# 24VBuckBoostConverterSM.net
KiCad netlist of a schematic drawn in Altium Designer
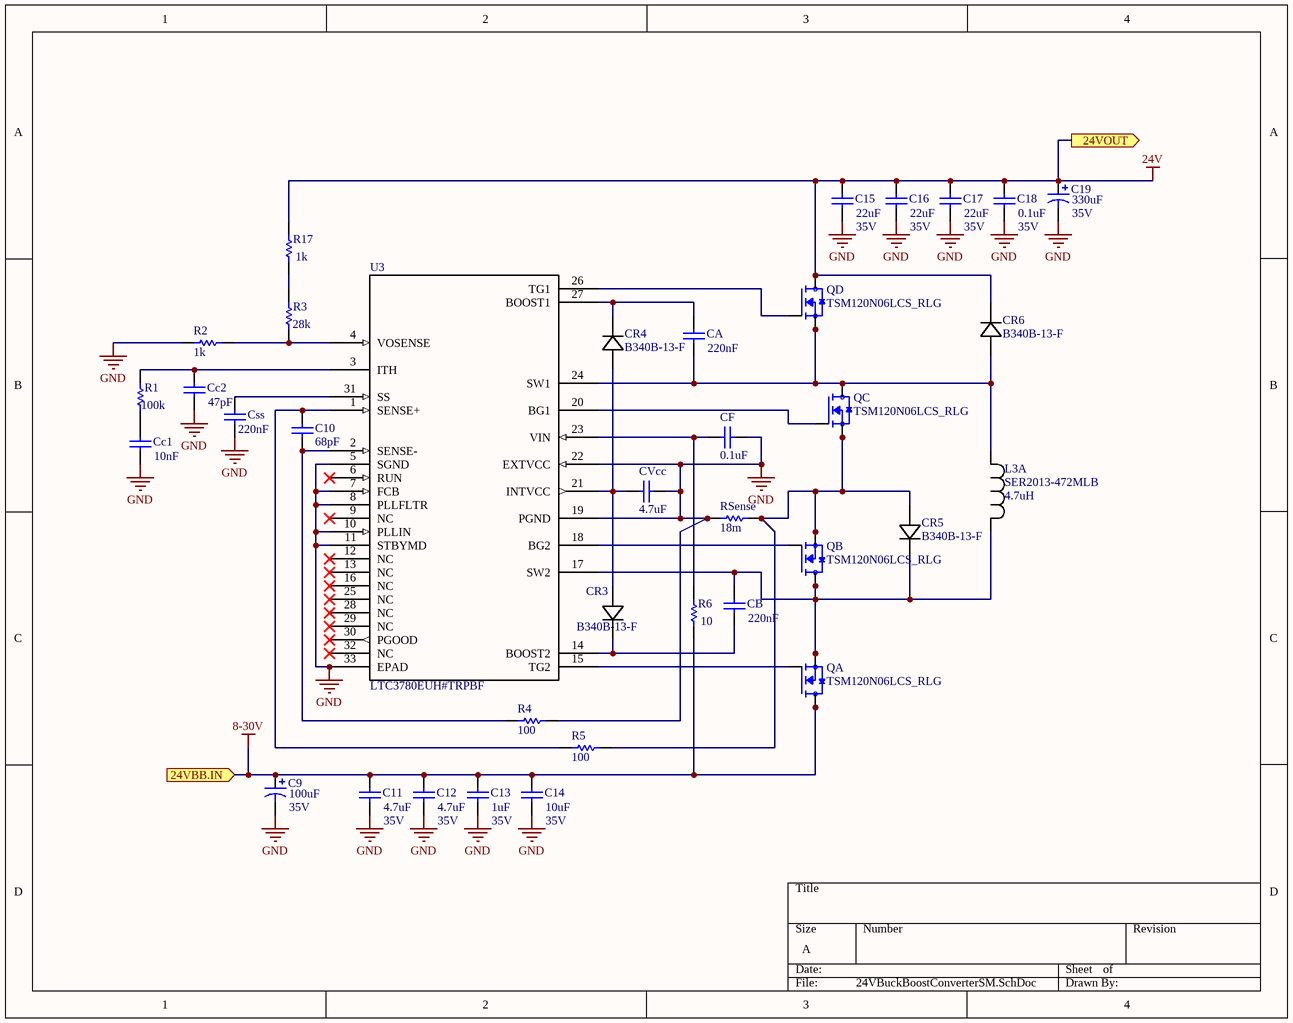
[diagram p0: 24VBuckBoostConverterSM.SchDoc]

(export (version "E")
  (design (tool "Eeschema 10.0.6"))
  (components
    (comp (ref "C9")
      (value "100uF")
      (footprint "RB7.6-15")
      (description "Polarized Capacitor (Radial)")
      (fields
        (field (name "VOLTAGE RATING") "35V")
        (field (name "Comment") "Cap Pol1")
        (field (name "PUBLISHER") "Altium Limited")
      )
      (libsource (lib "Miscellaneous Devices") (part "Cap Pol1"))
    )
    (comp (ref "C10")
      (value "68pF")
      (footprint "RAD-0.1")
      (description "Capacitor")
      (fields (field (name "Comment") "Cap") (field (name "PUBLISHER") "Altium Limited"))
      (libsource (lib "Miscellaneous Devices") (part "Cap"))
    )
    (comp (ref "C11")
      (value "4.7uF")
      (footprint "RAD-0.3")
      (description "Capacitor")
      (fields
        (field (name "VOLTAGE RATING") "35V")
        (field (name "Comment") "Cap")
        (field (name "PUBLISHER") "Altium Limited")
      )
      (libsource (lib "Miscellaneous Devices") (part "Cap"))
    )
    (comp (ref "C12")
      (value "4.7uF")
      (footprint "RAD-0.3")
      (description "Capacitor")
      (fields
        (field (name "VOLTAGE RATING") "35V")
        (field (name "Comment") "Cap")
        (field (name "PUBLISHER") "Altium Limited")
      )
      (libsource (lib "Miscellaneous Devices") (part "Cap"))
    )
    (comp (ref "C13")
      (value "1uF")
      (footprint "RAD-0.3")
      (description "Capacitor")
      (fields
        (field (name "VOLTAGE RATING") "35V")
        (field (name "Comment") "Cap")
        (field (name "PUBLISHER") "Altium Limited")
      )
      (libsource (lib "Miscellaneous Devices") (part "Cap"))
    )
    (comp (ref "C14")
      (value "10uF")
      (footprint "RAD-0.3")
      (description "Capacitor")
      (fields
        (field (name "VOLTAGE RATING") "35V")
        (field (name "Comment") "Cap")
        (field (name "PUBLISHER") "Altium Limited")
      )
      (libsource (lib "Miscellaneous Devices") (part "Cap"))
    )
    (comp (ref "C15")
      (value "22uF")
      (footprint "RAD-0.3")
      (description "Capacitor")
      (fields
        (field (name "VOLTAGE RATING") "35V")
        (field (name "Comment") "Cap")
        (field (name "PUBLISHER") "Altium Limited")
      )
      (libsource (lib "Miscellaneous Devices") (part "Cap"))
    )
    (comp (ref "C16")
      (value "22uF")
      (footprint "RAD-0.3")
      (description "Capacitor")
      (fields
        (field (name "VOLTAGE RATING") "35V")
        (field (name "Comment") "Cap")
        (field (name "PUBLISHER") "Altium Limited")
      )
      (libsource (lib "Miscellaneous Devices") (part "Cap"))
    )
    (comp (ref "C17")
      (value "22uF")
      (footprint "RAD-0.3")
      (description "Capacitor")
      (fields
        (field (name "VOLTAGE RATING") "35V")
        (field (name "Comment") "Cap")
        (field (name "PUBLISHER") "Altium Limited")
      )
      (libsource (lib "Miscellaneous Devices") (part "Cap"))
    )
    (comp (ref "C18")
      (value "0.1uF")
      (footprint "RAD-0.3")
      (description "Capacitor")
      (fields
        (field (name "VOLTAGE RATING") "35V")
        (field (name "Comment") "Cap")
        (field (name "PUBLISHER") "Altium Limited")
      )
      (libsource (lib "Miscellaneous Devices") (part "Cap"))
    )
    (comp (ref "C19")
      (value "330uF")
      (footprint "RB7.6-15")
      (description "Polarized Capacitor (Radial)")
      (fields
        (field (name "VOLTAGE RATING") "35V")
        (field (name "Comment") "Cap Pol1")
        (field (name "PUBLISHER") "Altium Limited")
      )
      (libsource (lib "Miscellaneous Devices") (part "Cap Pol1"))
    )
    (comp (ref "CA")
      (value "220nF")
      (footprint "RAD-0.1")
      (description "Capacitor")
      (fields (field (name "Comment") "Cap") (field (name "PUBLISHER") "Altium Limited"))
      (libsource (lib "Miscellaneous Devices") (part "Cap"))
    )
    (comp (ref "CB")
      (value "220nF")
      (footprint "RAD-0.1")
      (description "Capacitor")
      (fields (field (name "Comment") "Cap") (field (name "PUBLISHER") "Altium Limited"))
      (libsource (lib "Miscellaneous Devices") (part "Cap"))
    )
    (comp (ref "Cc1")
      (value "10nF")
      (footprint "RAD-0.1")
      (description "Capacitor")
      (fields (field (name "Comment") "Cap") (field (name "PUBLISHER") "Altium Limited"))
      (libsource (lib "Miscellaneous Devices") (part "Cap"))
    )
    (comp (ref "Cc2")
      (value "47pF")
      (footprint "RAD-0.2")
      (description "Capacitor")
      (fields (field (name "Comment") "Cap") (field (name "PUBLISHER") "Altium Limited"))
      (libsource (lib "Miscellaneous Devices") (part "Cap"))
    )
    (comp (ref "CF")
      (value "0.1uF")
      (footprint "RAD-0.1")
      (description "Capacitor")
      (fields (field (name "Comment") "Cap") (field (name "PUBLISHER") "Altium Limited"))
      (libsource (lib "Miscellaneous Devices") (part "Cap"))
    )
    (comp (ref "CR3")
      (value "B340B-13-F")
      (footprint "B340A-13-F")
      (description "No Description Available")
      (fields (field (name "COPYRIGHT") "Copyright (C) 2022 Ultra Librarian. All rights reserved."))
      (libsource (lib "B340B-13-F") (part "B340B-13-F"))
    )
    (comp (ref "CR4")
      (value "B340B-13-F")
      (footprint "B340A-13-F")
      (description "No Description Available")
      (fields (field (name "COPYRIGHT") "Copyright (C) 2022 Ultra Librarian. All rights reserved."))
      (libsource (lib "B340B-13-F") (part "B340B-13-F"))
    )
    (comp (ref "CR5")
      (value "B340B-13-F")
      (footprint "B340A-13-F")
      (description "No Description Available")
      (fields (field (name "COPYRIGHT") "Copyright (C) 2022 Ultra Librarian. All rights reserved."))
      (libsource (lib "B340B-13-F") (part "B340B-13-F"))
    )
    (comp (ref "CR6")
      (value "B340B-13-F")
      (footprint "B340A-13-F")
      (description "No Description Available")
      (fields (field (name "COPYRIGHT") "Copyright (C) 2022 Ultra Librarian. All rights reserved."))
      (libsource (lib "B340B-13-F") (part "B340B-13-F"))
    )
    (comp (ref "Css")
      (value "220nF")
      (footprint "RAD-0.1")
      (description "Capacitor")
      (fields (field (name "Comment") "Cap") (field (name "PUBLISHER") "Altium Limited"))
      (libsource (lib "Miscellaneous Devices") (part "Cap"))
    )
    (comp (ref "CVcc")
      (value "4.7uF")
      (footprint "RAD-0.1")
      (description "Capacitor")
      (fields (field (name "Comment") "Cap") (field (name "PUBLISHER") "Altium Limited"))
      (libsource (lib "Miscellaneous Devices") (part "Cap"))
    )
    (comp (ref "L3")
      (value "SER2013-472MLB")
      (footprint "SER2013-472MLB")
      (description "No Description Available")
      (fields
        (field (name "ALTIUM_VALUE") "4.7uH")
        (field (name "COPYRIGHT") "Copyright (C) 2022 Ultra Librarian. All rights reserved.")
      )
      (libsource (lib "SER2013-472MLB") (part "SER2013-472MLB"))
    )
    (comp (ref "QA")
      (value "TSM120N06LCS_RLG")
      (footprint "SOP127P600X200-8N")
      (description "60V, 23A, Single N-Channel Power MOSFET")
      (fields
        (field (name "MF") "Taiwan Semiconductor")
        (field (name "DIGI-KEY_PART_NUMBER") "TSM120N06LCSRLGTR-ND")
      )
      (libsource (lib "TSM120N06LCS_RLG") (part "TSM120N06LCS_RLG"))
    )
    (comp (ref "QB")
      (value "TSM120N06LCS_RLG")
      (footprint "SOP127P600X200-8N")
      (description "60V, 23A, Single N-Channel Power MOSFET")
      (fields
        (field (name "MF") "Taiwan Semiconductor")
        (field (name "DIGI-KEY_PART_NUMBER") "TSM120N06LCSRLGTR-ND")
      )
      (libsource (lib "TSM120N06LCS_RLG") (part "TSM120N06LCS_RLG"))
    )
    (comp (ref "QC")
      (value "TSM120N06LCS_RLG")
      (footprint "SOP127P600X200-8N")
      (description "60V, 23A, Single N-Channel Power MOSFET")
      (fields
        (field (name "MF") "Taiwan Semiconductor")
        (field (name "DIGI-KEY_PART_NUMBER") "TSM120N06LCSRLGTR-ND")
      )
      (libsource (lib "TSM120N06LCS_RLG") (part "TSM120N06LCS_RLG"))
    )
    (comp (ref "QD")
      (value "TSM120N06LCS_RLG")
      (footprint "SOP127P600X200-8N")
      (description "60V, 23A, Single N-Channel Power MOSFET")
      (fields
        (field (name "MF") "Taiwan Semiconductor")
        (field (name "DIGI-KEY_PART_NUMBER") "TSM120N06LCSRLGTR-ND")
      )
      (libsource (lib "TSM120N06LCS_RLG") (part "TSM120N06LCS_RLG"))
    )
    (comp (ref "R1")
      (value "100k")
      (footprint "AXIAL-0.3")
      (description "Resistor")
      (fields (field (name "Comment") "Res1") (field (name "PUBLISHER") "Altium Limited"))
      (libsource (lib "Miscellaneous Devices") (part "Res1"))
    )
    (comp (ref "R2")
      (value "1k")
      (footprint "AXIAL-0.3")
      (description "Resistor")
      (fields (field (name "Comment") "Res1") (field (name "PUBLISHER") "Altium Limited"))
      (libsource (lib "Miscellaneous Devices") (part "Res1"))
    )
    (comp (ref "R3")
      (value "28k")
      (footprint "AXIAL-0.3")
      (description "Resistor")
      (fields (field (name "Comment") "Res1") (field (name "PUBLISHER") "Altium Limited"))
      (libsource (lib "Miscellaneous Devices") (part "Res1"))
    )
    (comp (ref "R4")
      (value "100")
      (footprint "AXIAL-0.3")
      (description "Resistor")
      (fields (field (name "Comment") "Res1") (field (name "PUBLISHER") "Altium Limited"))
      (libsource (lib "Miscellaneous Devices") (part "Res1"))
    )
    (comp (ref "R5")
      (value "100")
      (footprint "AXIAL-0.3")
      (description "Resistor")
      (fields (field (name "Comment") "Res1") (field (name "PUBLISHER") "Altium Limited"))
      (libsource (lib "Miscellaneous Devices") (part "Res1"))
    )
    (comp (ref "R6")
      (value "10")
      (footprint "AXIAL-0.3")
      (description "Resistor")
      (fields (field (name "Comment") "Res1") (field (name "PUBLISHER") "Altium Limited"))
      (libsource (lib "Miscellaneous Devices") (part "Res1"))
    )
    (comp (ref "R17")
      (value "1k")
      (footprint "AXIAL-0.3")
      (description "Resistor")
      (fields (field (name "Comment") "Res1") (field (name "PUBLISHER") "Altium Limited"))
      (libsource (lib "Miscellaneous Devices") (part "Res1"))
    )
    (comp (ref "RSense")
      (value "18m")
      (footprint "AXIAL-0.3")
      (description "Resistor")
      (fields (field (name "Comment") "Res1") (field (name "PUBLISHER") "Altium Limited"))
      (libsource (lib "Miscellaneous Devices") (part "Res1"))
    )
    (comp (ref "U3")
      (value "LTC3780EUH#TRPBF")
      (footprint "LTC3780EUH")
      (libsource (lib "Parts") (part "LTC3780EUH#TRPBF"))
    )
  )
  (nets
    (net (code "1") (name "8-30V") (class "Default")
      (node (ref "C11") (pin "2") (pinfunction "2_2") (pintype "passive"))
      (node (ref "C12") (pin "2") (pinfunction "2_2") (pintype "passive"))
      (node (ref "C13") (pin "2") (pinfunction "2_2") (pintype "passive"))
      (node (ref "C14") (pin "2") (pinfunction "2_2") (pintype "passive"))
      (node (ref "C9") (pin "1") (pinfunction "1_1") (pintype "passive"))
      (node (ref "QA") (pin "5") (pinfunction "D_5") (pintype "passive"))
      (node (ref "QA") (pin "6") (pinfunction "D_6") (pintype "passive"))
      (node (ref "QA") (pin "7") (pinfunction "D_7") (pintype "passive"))
      (node (ref "QA") (pin "8") (pinfunction "D_8") (pintype "passive"))
      (node (ref "R6") (pin "1") (pinfunction "1_1") (pintype "passive"))
    )
    (net (code "2") (name "24V") (class "Default")
      (node (ref "C15") (pin "2") (pinfunction "2_2") (pintype "passive"))
      (node (ref "C16") (pin "2") (pinfunction "2_2") (pintype "passive"))
      (node (ref "C17") (pin "2") (pinfunction "2_2") (pintype "passive"))
      (node (ref "C18") (pin "2") (pinfunction "2_2") (pintype "passive"))
      (node (ref "C19") (pin "1") (pinfunction "1_1") (pintype "passive"))
      (node (ref "CR6") (pin "1") (pinfunction "1_1") (pintype "passive"))
      (node (ref "QD") (pin "5") (pinfunction "D_5") (pintype "passive"))
      (node (ref "QD") (pin "6") (pinfunction "D_6") (pintype "passive"))
      (node (ref "QD") (pin "7") (pinfunction "D_7") (pintype "passive"))
      (node (ref "QD") (pin "8") (pinfunction "D_8") (pintype "passive"))
      (node (ref "R17") (pin "2") (pinfunction "2_2") (pintype "passive"))
    )
    (net (code "3") (name "GND") (class "Default")
      (node (ref "C11") (pin "1") (pinfunction "1_1") (pintype "passive"))
      (node (ref "C12") (pin "1") (pinfunction "1_1") (pintype "passive"))
      (node (ref "C13") (pin "1") (pinfunction "1_1") (pintype "passive"))
      (node (ref "C14") (pin "1") (pinfunction "1_1") (pintype "passive"))
      (node (ref "C15") (pin "1") (pinfunction "1_1") (pintype "passive"))
      (node (ref "C16") (pin "1") (pinfunction "1_1") (pintype "passive"))
      (node (ref "C17") (pin "1") (pinfunction "1_1") (pintype "passive"))
      (node (ref "C18") (pin "1") (pinfunction "1_1") (pintype "passive"))
      (node (ref "C19") (pin "2") (pinfunction "2_2") (pintype "passive"))
      (node (ref "C9") (pin "2") (pinfunction "2_2") (pintype "passive"))
      (node (ref "CF") (pin "1") (pinfunction "1_1") (pintype "passive"))
      (node (ref "CVcc") (pin "1") (pinfunction "1_1") (pintype "passive"))
      (node (ref "Cc1") (pin "1") (pinfunction "1_1") (pintype "passive"))
      (node (ref "Cc2") (pin "1") (pinfunction "1_1") (pintype "passive"))
      (node (ref "Css") (pin "1") (pinfunction "1_1") (pintype "passive"))
      (node (ref "R2") (pin "2") (pinfunction "2_2") (pintype "passive"))
      (node (ref "R4") (pin "1") (pinfunction "1_1") (pintype "passive"))
      (node (ref "RSense") (pin "2") (pinfunction "2_2") (pintype "passive"))
      (node (ref "U3") (pin "10") (pinfunction "PLLIN_10") (pintype "input"))
      (node (ref "U3") (pin "11") (pinfunction "STBYMD_11") (pintype "passive"))
      (node (ref "U3") (pin "19") (pinfunction "PGND_19") (pintype "power_in"))
      (node (ref "U3") (pin "22") (pinfunction "EXTVCC_22") (pintype "input"))
      (node (ref "U3") (pin "33") (pinfunction "EPAD_33") (pintype "passive"))
      (node (ref "U3") (pin "5") (pinfunction "SGND_5") (pintype "power_in"))
      (node (ref "U3") (pin "7") (pinfunction "FCB_7") (pintype "input"))
      (node (ref "U3") (pin "8") (pinfunction "PLLFLTR_8") (pintype "passive"))
    )
    (net (code "4") (name "Net-(CR5-Pad2)") (class "Default")
      (node (ref "CR5") (pin "2") (pinfunction "2_2") (pintype "passive"))
      (node (ref "QB") (pin "1") (pinfunction "S_1") (pintype "passive"))
      (node (ref "QB") (pin "2") (pinfunction "S_2") (pintype "passive"))
      (node (ref "QB") (pin "3") (pinfunction "S_3") (pintype "passive"))
      (node (ref "QC") (pin "1") (pinfunction "S_1") (pintype "passive"))
      (node (ref "QC") (pin "2") (pinfunction "S_2") (pintype "passive"))
      (node (ref "QC") (pin "3") (pinfunction "S_3") (pintype "passive"))
      (node (ref "R5") (pin "1") (pinfunction "1_1") (pintype "passive"))
      (node (ref "RSense") (pin "1") (pinfunction "1_1") (pintype "passive"))
    )
    (net (code "5") (name "Net-(Cc1-Pad2)") (class "Default")
      (node (ref "Cc1") (pin "2") (pinfunction "2_2") (pintype "passive"))
      (node (ref "R1") (pin "1") (pinfunction "1_1") (pintype "passive"))
    )
    (net (code "6") (name "Net-(QA-G)") (class "Default")
      (node (ref "QA") (pin "4") (pinfunction "G_4") (pintype "passive"))
      (node (ref "U3") (pin "15") (pinfunction "TG2_15") (pintype "passive"))
    )
    (net (code "7") (name "Net-(QB-G)") (class "Default")
      (node (ref "QB") (pin "4") (pinfunction "G_4") (pintype "passive"))
      (node (ref "U3") (pin "18") (pinfunction "BG2_18") (pintype "passive"))
    )
    (net (code "8") (name "Net-(QC-G)") (class "Default")
      (node (ref "QC") (pin "4") (pinfunction "G_4") (pintype "passive"))
      (node (ref "U3") (pin "20") (pinfunction "BG1_20") (pintype "passive"))
    )
    (net (code "9") (name "Net-(QD-G)") (class "Default")
      (node (ref "QD") (pin "4") (pinfunction "G_4") (pintype "passive"))
      (node (ref "U3") (pin "26") (pinfunction "TG1_26") (pintype "passive"))
    )
    (net (code "10") (name "Net-(R17-Pad1)") (class "Default")
      (node (ref "R17") (pin "1") (pinfunction "1_1") (pintype "passive"))
      (node (ref "R3") (pin "2") (pinfunction "2_2") (pintype "passive"))
    )
    (net (code "11") (name "Net-(U3-BOOST1)") (class "Default")
      (node (ref "CA") (pin "2") (pinfunction "2_2") (pintype "passive"))
      (node (ref "CR4") (pin "1") (pinfunction "1_1") (pintype "passive"))
      (node (ref "U3") (pin "27") (pinfunction "BOOST1_27") (pintype "passive"))
    )
    (net (code "12") (name "Net-(U3-BOOST2)") (class "Default")
      (node (ref "CB") (pin "1") (pinfunction "1_1") (pintype "passive"))
      (node (ref "CR3") (pin "1") (pinfunction "1_1") (pintype "passive"))
      (node (ref "U3") (pin "14") (pinfunction "BOOST2_14") (pintype "passive"))
    )
    (net (code "13") (name "Net-(U3-INTVCC)") (class "Default")
      (node (ref "CR3") (pin "2") (pinfunction "2_2") (pintype "passive"))
      (node (ref "CR4") (pin "2") (pinfunction "2_2") (pintype "passive"))
      (node (ref "CVcc") (pin "2") (pinfunction "2_2") (pintype "passive"))
      (node (ref "U3") (pin "21") (pinfunction "INTVCC_21") (pintype "output"))
    )
    (net (code "14") (name "Net-(U3-ITH)") (class "Default")
      (node (ref "Cc2") (pin "2") (pinfunction "2_2") (pintype "passive"))
      (node (ref "R1") (pin "2") (pinfunction "2_2") (pintype "passive"))
      (node (ref "U3") (pin "3") (pinfunction "ITH_3") (pintype "passive"))
    )
    (net (code "15") (name "Net-(U3-SENSE+)") (class "Default")
      (node (ref "C10") (pin "1") (pinfunction "1_1") (pintype "passive"))
      (node (ref "R5") (pin "2") (pinfunction "2_2") (pintype "passive"))
      (node (ref "U3") (pin "1") (pinfunction "SENSE+_1") (pintype "input"))
    )
    (net (code "16") (name "Net-(U3-SENSE-)") (class "Default")
      (node (ref "C10") (pin "2") (pinfunction "2_2") (pintype "passive"))
      (node (ref "R4") (pin "2") (pinfunction "2_2") (pintype "passive"))
      (node (ref "U3") (pin "2") (pinfunction "SENSE-_2") (pintype "input"))
    )
    (net (code "17") (name "Net-(U3-SS)") (class "Default")
      (node (ref "Css") (pin "2") (pinfunction "2_2") (pintype "passive"))
      (node (ref "U3") (pin "31") (pinfunction "SS_31") (pintype "input"))
    )
    (net (code "18") (name "Net-(U3-SW1)") (class "Default")
      (node (ref "CA") (pin "1") (pinfunction "1_1") (pintype "passive"))
      (node (ref "CR6") (pin "2") (pinfunction "2_2") (pintype "passive"))
      (node (ref "L3") (pin "2") (pinfunction "2_2") (pintype "passive"))
      (node (ref "QC") (pin "5") (pinfunction "D_5") (pintype "passive"))
      (node (ref "QC") (pin "6") (pinfunction "D_6") (pintype "passive"))
      (node (ref "QC") (pin "7") (pinfunction "D_7") (pintype "passive"))
      (node (ref "QC") (pin "8") (pinfunction "D_8") (pintype "passive"))
      (node (ref "QD") (pin "1") (pinfunction "S_1") (pintype "passive"))
      (node (ref "QD") (pin "2") (pinfunction "S_2") (pintype "passive"))
      (node (ref "QD") (pin "3") (pinfunction "S_3") (pintype "passive"))
      (node (ref "U3") (pin "24") (pinfunction "SW1_24") (pintype "passive"))
    )
    (net (code "19") (name "Net-(U3-SW2)") (class "Default")
      (node (ref "CB") (pin "2") (pinfunction "2_2") (pintype "passive"))
      (node (ref "CR5") (pin "1") (pinfunction "1_1") (pintype "passive"))
      (node (ref "L3") (pin "1") (pinfunction "1_1") (pintype "passive"))
      (node (ref "QA") (pin "1") (pinfunction "S_1") (pintype "passive"))
      (node (ref "QA") (pin "2") (pinfunction "S_2") (pintype "passive"))
      (node (ref "QA") (pin "3") (pinfunction "S_3") (pintype "passive"))
      (node (ref "QB") (pin "5") (pinfunction "D_5") (pintype "passive"))
      (node (ref "QB") (pin "6") (pinfunction "D_6") (pintype "passive"))
      (node (ref "QB") (pin "7") (pinfunction "D_7") (pintype "passive"))
      (node (ref "QB") (pin "8") (pinfunction "D_8") (pintype "passive"))
      (node (ref "U3") (pin "17") (pinfunction "SW2_17") (pintype "passive"))
    )
    (net (code "20") (name "Net-(U3-VIN)") (class "Default")
      (node (ref "CF") (pin "2") (pinfunction "2_2") (pintype "passive"))
      (node (ref "R6") (pin "2") (pinfunction "2_2") (pintype "passive"))
      (node (ref "U3") (pin "23") (pinfunction "VIN_23") (pintype "input"))
    )
    (net (code "21") (name "Net-(U3-VOSENSE)") (class "Default")
      (node (ref "R2") (pin "1") (pinfunction "1_1") (pintype "passive"))
      (node (ref "R3") (pin "1") (pinfunction "1_1") (pintype "passive"))
      (node (ref "U3") (pin "4") (pinfunction "VOSENSE_4") (pintype "input"))
    )
    (net (code "22") (name "unconnected-(U3-NC-Pad9)") (class "Default")
      (node (ref "U3") (pin "9") (pinfunction "NC_9") (pintype "passive+no_connect"))
    )
    (net (code "23") (name "unconnected-(U3-NC-Pad12)") (class "Default")
      (node (ref "U3") (pin "12") (pinfunction "NC_12") (pintype "passive+no_connect"))
    )
    (net (code "24") (name "unconnected-(U3-NC-Pad13)") (class "Default")
      (node (ref "U3") (pin "13") (pinfunction "NC_13") (pintype "passive+no_connect"))
    )
    (net (code "25") (name "unconnected-(U3-NC-Pad16)") (class "Default")
      (node (ref "U3") (pin "16") (pinfunction "NC_16") (pintype "passive+no_connect"))
    )
    (net (code "26") (name "unconnected-(U3-NC-Pad25)") (class "Default")
      (node (ref "U3") (pin "25") (pinfunction "NC_25") (pintype "passive+no_connect"))
    )
    (net (code "27") (name "unconnected-(U3-NC-Pad28)") (class "Default")
      (node (ref "U3") (pin "28") (pinfunction "NC_28") (pintype "passive+no_connect"))
    )
    (net (code "28") (name "unconnected-(U3-NC-Pad29)") (class "Default")
      (node (ref "U3") (pin "29") (pinfunction "NC_29") (pintype "passive+no_connect"))
    )
    (net (code "29") (name "unconnected-(U3-NC-Pad32)") (class "Default")
      (node (ref "U3") (pin "32") (pinfunction "NC_32") (pintype "passive+no_connect"))
    )
    (net (code "30") (name "unconnected-(U3-PGOOD-Pad30)") (class "Default")
      (node (ref "U3") (pin "30") (pinfunction "PGOOD_30") (pintype "output+no_connect"))
    )
    (net (code "31") (name "unconnected-(U3-RUN-Pad6)") (class "Default")
      (node (ref "U3") (pin "6") (pinfunction "RUN_6") (pintype "input+no_connect"))
    )
  )
)
